# LittleBoard.net
KiCad netlist of a schematic drawn in Altium Designer
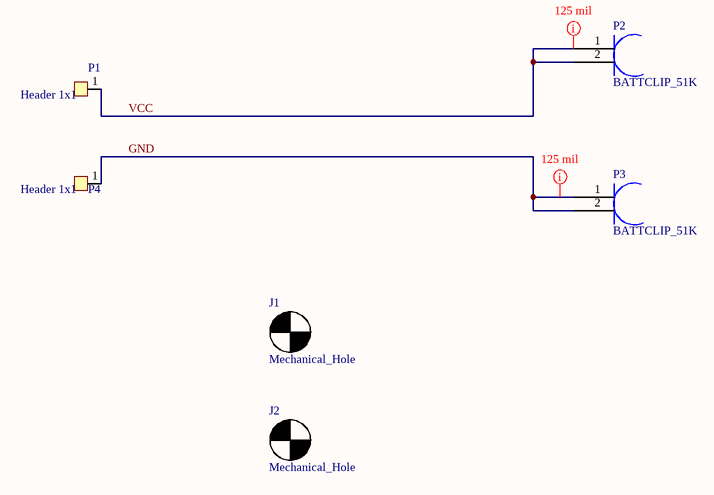
[diagram p0: LittleBoard.SchDoc]

(export (version "E")
  (design (tool "Eeschema 10.0.6"))
  (components
    (comp (ref "J1")
      (value "Mechanical_Hole")
      (footprint "#4_Screw_Hole")
      (description "A mechanical hole for mounting the board")
      (libsource (lib "mrone") (part "Mechanical_Hole"))
    )
    (comp (ref "J2")
      (value "Mechanical_Hole")
      (footprint "#4_Screw_Hole")
      (description "A mechanical hole for mounting the board")
      (libsource (lib "mrone") (part "Mechanical_Hole"))
    )
    (comp (ref "P1") (value "Header 1x1") (footprint "HDR1X1") (libsource (lib "mrone") (part "Header 1x1")))
    (comp (ref "P2")
      (value "BATTCLIP_51K")
      (footprint "BATTCLIP_51K")
      (libsource (lib "mrone") (part "BATTCLIP_51K"))
    )
    (comp (ref "P3")
      (value "BATTCLIP_51K")
      (footprint "BATTCLIP_51K")
      (libsource (lib "mrone") (part "BATTCLIP_51K"))
    )
    (comp (ref "P4") (value "Header 1x1") (footprint "HDR1X1") (libsource (lib "mrone") (part "Header 1x1")))
  )
  (nets
    (net (code "1") (name "/GND") (class "Default")
      (node (ref "P3") (pin "1") (pintype "power_in"))
      (node (ref "P3") (pin "2") (pintype "power_in"))
      (node (ref "P4") (pin "1") (pintype "passive"))
    )
    (net (code "2") (name "/VCC") (class "Default")
      (node (ref "P1") (pin "1") (pintype "passive"))
      (node (ref "P2") (pin "1") (pintype "power_in"))
      (node (ref "P2") (pin "2") (pintype "power_in"))
    )
  )
)
